# cell_simulator.net
KiCad netlist of a schematic drawn in Altium Designer
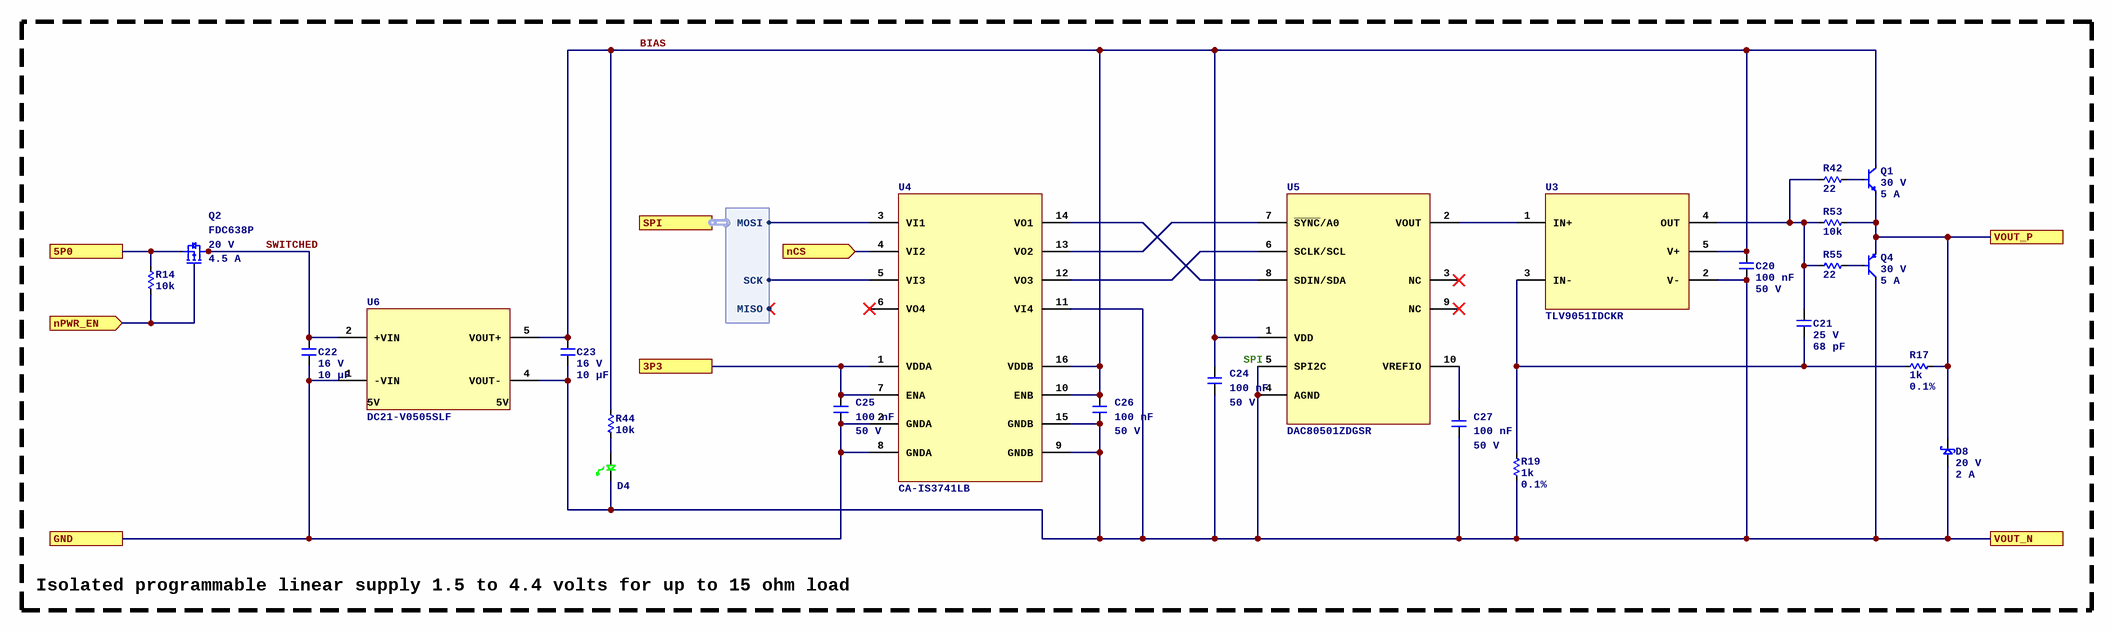
[diagram p0: cell_simulator.SchDoc]

(export (version "E")
  (design (tool "Eeschema 10.0.6"))
  (components
    (comp (ref "C20")
      (value "CL05B104KB54PNC")
      (footprint "C0402")
      (fields
        (field (name "CAPACITANCE") "100 nF")
        (field (name "MANUFACTURER") "Samsung Electro-Mechanics")
        (field (name "VOLTAGE RATING") "50 V")
      )
      (libsource (lib "database") (part "__template_cap"))
    )
    (comp (ref "C21")
      (value "CBR04C680F3GAC")
      (footprint "C0402")
      (fields
        (field (name "VOLTAGE RATING") "25 V")
        (field (name "CAPACITANCE") "68 pF")
        (field (name "MANUFACTURER") "KEMET")
      )
      (libsource (lib "database") (part "__template_cap"))
    )
    (comp (ref "C22")
      (value "CL21B106KOQNNNE")
      (footprint "C0805")
      (fields
        (field (name "VOLTAGE RATING") "16 V")
        (field (name "CAPACITANCE") "10 µF")
        (field (name "MANUFACTURER") "Samsung Electro-Mechanics")
      )
      (libsource (lib "database") (part "__template_cap"))
    )
    (comp (ref "C23")
      (value "CL21B106KOQNNNE")
      (footprint "C0805")
      (fields
        (field (name "VOLTAGE RATING") "16 V")
        (field (name "CAPACITANCE") "10 µF")
        (field (name "MANUFACTURER") "Samsung Electro-Mechanics")
      )
      (libsource (lib "database") (part "__template_cap"))
    )
    (comp (ref "C24")
      (value "CL05B104KB54PNC")
      (footprint "C0402")
      (fields
        (field (name "CAPACITANCE") "100 nF")
        (field (name "MANUFACTURER") "Samsung Electro-Mechanics")
        (field (name "VOLTAGE RATING") "50 V")
      )
      (libsource (lib "database") (part "__template_cap"))
    )
    (comp (ref "C25")
      (value "CL05B104KB54PNC")
      (footprint "C0402")
      (fields
        (field (name "CAPACITANCE") "100 nF")
        (field (name "MANUFACTURER") "Samsung Electro-Mechanics")
        (field (name "VOLTAGE RATING") "50 V")
      )
      (libsource (lib "database") (part "__template_cap"))
    )
    (comp (ref "C26")
      (value "CL05B104KB54PNC")
      (footprint "C0402")
      (fields
        (field (name "CAPACITANCE") "100 nF")
        (field (name "MANUFACTURER") "Samsung Electro-Mechanics")
        (field (name "VOLTAGE RATING") "50 V")
      )
      (libsource (lib "database") (part "__template_cap"))
    )
    (comp (ref "C27")
      (value "CL05B104KB54PNC")
      (footprint "C0402")
      (fields
        (field (name "CAPACITANCE") "100 nF")
        (field (name "MANUFACTURER") "Samsung Electro-Mechanics")
        (field (name "VOLTAGE RATING") "50 V")
      )
      (libsource (lib "database") (part "__template_cap"))
    )
    (comp (ref "D4")
      (value "LTST-C190GKT")
      (footprint "LED_0603P_GREEN")
      (description "LED GREEN CLEAR 0603 SMD")
      (fields (field (name "MANUFACTURER") "Lite-On Inc"))
      (libsource (lib "database") (part "__template_led_green"))
    )
    (comp (ref "D8")
      (value "MSS2P2-M3/89A")
      (footprint "ESMP")
      (description "DIODE SCHOTTKY 20V 2A MICROSMP")
      (fields
        (field (name "MANUFACTURER") "Vishay Semiconductor Diodes Division")
        (field (name "VR") "20 V")
        (field (name "CURRENT") "2 A")
      )
      (libsource (lib "database") (part "__template_diode_schottky"))
    )
    (comp (ref "Q1")
      (value "2SCR572D3TL1")
      (footprint "TO-252-3")
      (description "NPN power transistor, 30 V, 5 A, low VCE(sat), TO-252-3")
      (fields
        (field (name "VOLTAGE") "30 V")
        (field (name "CURRENT") "5 A")
        (field (name "MANUFACTURER") "ROHM Semiconductor")
      )
      (libsource (lib "database") (part "2SCR572D3TL1"))
    )
    (comp (ref "Q2")
      (value "FDC638P")
      (footprint "6SOT23")
      (description "MOSFET P-CH 20V 4.5A SSOT-6")
      (fields
        (field (name "MANUFACTURER") "onsemi")
        (field (name "VOLTAGE") "20 V")
        (field (name "CURRENT") "4.5 A")
      )
      (libsource (lib "database") (part "FDC638P"))
    )
    (comp (ref "Q4")
      (value "2SAR572D3TL1")
      (footprint "TO-252-3")
      (description "PNP power transistor, 30 V, 5 A, low VCE(sat), TO-252-3")
      (fields
        (field (name "VOLTAGE") "30 V")
        (field (name "CURRENT") "5 A")
        (field (name "MANUFACTURER") "ROHM Semiconductor")
      )
      (libsource (lib "database") (part "2SAR572D3TL1"))
    )
    (comp (ref "R14")
      (value "10k")
      (footprint "R0402")
      (fields
        (field (name "TOLERANCE") "1%")
        (field (name "MANUFACTURER PART NUMBER") "0402WGF1002TCE")
        (field (name "MANUFACTURER") "UNI-ROYAL(Uniroyal Elec)")
      )
      (libsource (lib "database") (part "__template_resistor"))
    )
    (comp (ref "R17")
      (value "1k")
      (footprint "R0402")
      (fields
        (field (name "MANUFACTURER PART NUMBER") "ERA2AEB102X")
        (field (name "MANUFACTURER") "PANASONIC")
        (field (name "TOLERANCE") "0.1%")
      )
      (libsource (lib "database") (part "__template_resistor"))
    )
    (comp (ref "R19")
      (value "1k")
      (footprint "R0402")
      (fields
        (field (name "MANUFACTURER PART NUMBER") "ERA2AEB102X")
        (field (name "MANUFACTURER") "PANASONIC")
        (field (name "TOLERANCE") "0.1%")
      )
      (libsource (lib "database") (part "__template_resistor"))
    )
    (comp (ref "R42")
      (value "22")
      (footprint "R0402")
      (fields
        (field (name "MANUFACTURER PART NUMBER") "0402WGF220JTCE")
        (field (name "MANUFACTURER") "UNI-ROYAL(Uniroyal Elec)")
        (field (name "TOLERANCE") "1%")
      )
      (libsource (lib "database") (part "__template_resistor"))
    )
    (comp (ref "R44")
      (value "10k")
      (footprint "R0402")
      (fields
        (field (name "TOLERANCE") "1%")
        (field (name "MANUFACTURER PART NUMBER") "0402WGF1002TCE")
        (field (name "MANUFACTURER") "UNI-ROYAL(Uniroyal Elec)")
      )
      (libsource (lib "database") (part "__template_resistor"))
    )
    (comp (ref "R53")
      (value "10k")
      (footprint "R0402")
      (fields
        (field (name "MANUFACTURER PART NUMBER") "0402WGF1002TCE")
        (field (name "MANUFACTURER") "UNI-ROYAL(Uniroyal Elec)")
        (field (name "TOLERANCE") "1%")
      )
      (libsource (lib "database") (part "__template_resistor"))
    )
    (comp (ref "R55")
      (value "22")
      (footprint "R0402")
      (fields
        (field (name "MANUFACTURER PART NUMBER") "0402WGF220JTCE")
        (field (name "MANUFACTURER") "UNI-ROYAL(Uniroyal Elec)")
        (field (name "TOLERANCE") "1%")
      )
      (libsource (lib "database") (part "__template_resistor"))
    )
    (comp (ref "U3")
      (value "TLV9051IDCKR")
      (footprint "5SC70")
      (description "Single 5 MHz rail-to-rail input/output operational amplifier, 15 V/µs slew rate, SC70-5")
      (fields (field (name "MANUFACTURER") "Texas Instruments"))
      (libsource (lib "database") (part "TLV9051IDCKR"))
    )
    (comp (ref "U4")
      (value "CA-IS3741LB")
      (footprint "16SSOP635")
      (description "150Mbps 150kV/µs 2.5V~5.5V 2.5V~5.5V 3 3750 Low Level SSOP-16-150mil Digital Isolators ROHS")
      (fields (field (name "MANUFACTURER") "Chipanalog"))
      (libsource (lib "database") (part "CA-IS3741LB"))
    )
    (comp (ref "U5")
      (value "DAC80501ZDGSR")
      (footprint "TI_DGS")
      (description "16 Bit Digital to Analog Converter 1 10-VSSOP, zero output at startup")
      (fields (field (name "MANUFACTURER") "Texas Instruments"))
      (libsource (lib "database") (part "DAC80501MDGSR"))
    )
    (comp (ref "U6")
      (value "DC21-V0505SLF")
      (footprint "HALO_DC21")
      (description "Isolated Module DC DC Converter 1 Output 5V 400mA 4.5V - 5.5V Input")
      (fields (field (name "MANUFACTURER") "HALO Electronics, Inc."))
      (libsource (lib "database") (part "DC21-V0505SLF"))
    )
  )
  (nets
    (net (code "2") (name "/3P3") (class "Default")
      (node (ref "C25") (pin "1") (pintype "passive"))
      (node (ref "U4") (pin "1") (pinfunction "VDDA_1") (pintype "passive"))
      (node (ref "U4") (pin "7") (pinfunction "ENA_7") (pintype "passive"))
    )
    (net (code "3") (name "/5P0") (class "Default")
      (node (ref "Q2") (pin "4") (pintype "passive"))
      (node (ref "R14") (pin "2") (pintype "passive"))
    )
    (net (code "4") (name "/BIAS") (class "Default")
      (node (ref "C20") (pin "1") (pintype "passive"))
      (node (ref "C23") (pin "1") (pintype "passive"))
      (node (ref "C24") (pin "1") (pintype "passive"))
      (node (ref "C26") (pin "1") (pintype "passive"))
      (node (ref "Q1") (pin "4") (pinfunction "C_4") (pintype "passive"))
      (node (ref "R44") (pin "2") (pintype "passive"))
      (node (ref "U3") (pin "5") (pinfunction "V+_5") (pintype "passive"))
      (node (ref "U4") (pin "10") (pinfunction "ENB_10") (pintype "passive"))
      (node (ref "U4") (pin "16") (pinfunction "VDDB_16") (pintype "passive"))
      (node (ref "U5") (pin "1") (pinfunction "VDD_1") (pintype "passive"))
      (node (ref "U6") (pin "5") (pinfunction "VOUT+_5") (pintype "passive"))
    )
    (net (code "5") (name "/GND") (class "Default")
      (node (ref "C22") (pin "2") (pintype "passive"))
      (node (ref "C25") (pin "2") (pintype "passive"))
      (node (ref "U4") (pin "2") (pinfunction "GNDA_2") (pintype "passive"))
      (node (ref "U4") (pin "8") (pinfunction "GNDA_8") (pintype "passive"))
      (node (ref "U6") (pin "1") (pinfunction "-VIN_1") (pintype "passive"))
    )
    (net (code "6") (name "/MOSI") (class "Default")
      (node (ref "U4") (pin "3") (pinfunction "VI1_3") (pintype "passive"))
    )
    (net (code "7") (name "/SCK") (class "Default")
      (node (ref "U4") (pin "5") (pinfunction "VI3_5") (pintype "passive"))
    )
    (net (code "8") (name "/SWITCHED") (class "Default")
      (node (ref "C22") (pin "1") (pintype "passive"))
      (node (ref "Q2") (pin "1") (pintype "passive"))
      (node (ref "Q2") (pin "2") (pintype "passive"))
      (node (ref "Q2") (pin "5") (pintype "passive"))
      (node (ref "Q2") (pin "6") (pintype "passive"))
      (node (ref "U6") (pin "2") (pinfunction "+VIN_2") (pintype "passive"))
    )
    (net (code "9") (name "/VOUT_N") (class "Default")
      (node (ref "C20") (pin "2") (pintype "passive"))
      (node (ref "C23") (pin "2") (pintype "passive"))
      (node (ref "C24") (pin "2") (pintype "passive"))
      (node (ref "C26") (pin "2") (pintype "passive"))
      (node (ref "C27") (pin "2") (pintype "passive"))
      (node (ref "D4") (pin "2") (pintype "passive"))
      (node (ref "D8") (pin "1") (pintype "passive"))
      (node (ref "Q4") (pin "4") (pinfunction "C_4") (pintype "passive"))
      (node (ref "R19") (pin "1") (pintype "passive"))
      (node (ref "U3") (pin "2") (pinfunction "V-_2") (pintype "passive"))
      (node (ref "U4") (pin "11") (pinfunction "VI4_11") (pintype "passive"))
      (node (ref "U4") (pin "15") (pinfunction "GNDB_15") (pintype "passive"))
      (node (ref "U4") (pin "9") (pinfunction "GNDB_9") (pintype "passive"))
      (node (ref "U5") (pin "4") (pinfunction "AGND_4") (pintype "passive"))
      (node (ref "U5") (pin "5") (pinfunction "SPI2C_5") (pintype "passive"))
      (node (ref "U6") (pin "4") (pinfunction "VOUT-_4") (pintype "passive"))
    )
    (net (code "10") (name "/VOUT_P") (class "Default")
      (node (ref "D8") (pin "2") (pintype "passive"))
      (node (ref "Q1") (pin "3") (pinfunction "E_3") (pintype "passive"))
      (node (ref "Q4") (pin "3") (pinfunction "E_3") (pintype "passive"))
      (node (ref "R17") (pin "1") (pintype "passive"))
      (node (ref "R53") (pin "1") (pintype "passive"))
    )
    (net (code "11") (name "/nCS") (class "Default")
      (node (ref "U4") (pin "4") (pinfunction "VI2_4") (pintype "passive"))
    )
    (net (code "12") (name "/nPWR_EN") (class "Default")
      (node (ref "Q2") (pin "3") (pintype "passive"))
      (node (ref "R14") (pin "1") (pintype "passive"))
    )
    (net (code "14") (name "Net-(D4-Pad1)") (class "Default")
      (node (ref "D4") (pin "1") (pintype "passive"))
      (node (ref "R44") (pin "1") (pintype "passive"))
    )
    (net (code "15") (name "Net-(Q1-B)") (class "Default")
      (node (ref "Q1") (pin "1") (pinfunction "B_1") (pintype "passive"))
      (node (ref "R42") (pin "1") (pintype "passive"))
    )
    (net (code "16") (name "Net-(Q4-B)") (class "Default")
      (node (ref "Q4") (pin "1") (pinfunction "B_1") (pintype "passive"))
      (node (ref "R55") (pin "1") (pintype "passive"))
    )
    (net (code "17") (name "Net-(U3-IN+)") (class "Default")
      (node (ref "U3") (pin "1") (pinfunction "IN+_1") (pintype "passive"))
      (node (ref "U5") (pin "2") (pinfunction "VOUT_2") (pintype "passive"))
    )
    (net (code "18") (name "Net-(U3-IN-)") (class "Default")
      (node (ref "C21") (pin "2") (pintype "passive"))
      (node (ref "R17") (pin "2") (pintype "passive"))
      (node (ref "R19") (pin "2") (pintype "passive"))
      (node (ref "U3") (pin "3") (pinfunction "IN-_3") (pintype "passive"))
    )
    (net (code "19") (name "Net-(U3-OUT)") (class "Default")
      (node (ref "C21") (pin "1") (pintype "passive"))
      (node (ref "R42") (pin "2") (pintype "passive"))
      (node (ref "R53") (pin "2") (pintype "passive"))
      (node (ref "R55") (pin "2") (pintype "passive"))
      (node (ref "U3") (pin "4") (pinfunction "OUT_4") (pintype "passive"))
    )
    (net (code "20") (name "Net-(U4-VO1)") (class "Default")
      (node (ref "U4") (pin "14") (pinfunction "VO1_14") (pintype "passive"))
      (node (ref "U5") (pin "8") (pinfunction "SDIN/SDA_8") (pintype "passive"))
    )
    (net (code "21") (name "Net-(U4-VO2)") (class "Default")
      (node (ref "U4") (pin "13") (pinfunction "VO2_13") (pintype "passive"))
      (node (ref "U5") (pin "7") (pinfunction "~{SYNC}/A0_7") (pintype "passive"))
    )
    (net (code "22") (name "Net-(U4-VO3)") (class "Default")
      (node (ref "U4") (pin "12") (pinfunction "VO3_12") (pintype "passive"))
      (node (ref "U5") (pin "6") (pinfunction "SCLK/SCL_6") (pintype "passive"))
    )
    (net (code "23") (name "Net-(U5-VREFIO)") (class "Default")
      (node (ref "C27") (pin "1") (pintype "passive"))
      (node (ref "U5") (pin "10") (pinfunction "VREFIO_10") (pintype "passive"))
    )
    (net (code "24") (name "unconnected-(U4-VO4-Pad6)") (class "Default")
      (node (ref "U4") (pin "6") (pinfunction "VO4_6") (pintype "passive+no_connect"))
    )
    (net (code "25") (name "unconnected-(U5-NC-Pad3)") (class "Default")
      (node (ref "U5") (pin "3") (pinfunction "NC_3") (pintype "passive+no_connect"))
    )
    (net (code "26") (name "unconnected-(U5-NC-Pad9)") (class "Default")
      (node (ref "U5") (pin "9") (pinfunction "NC_9") (pintype "passive+no_connect"))
    )
  )
)
